# USB_OTG_FS.net
KiCad netlist of a schematic drawn in Altium Designer
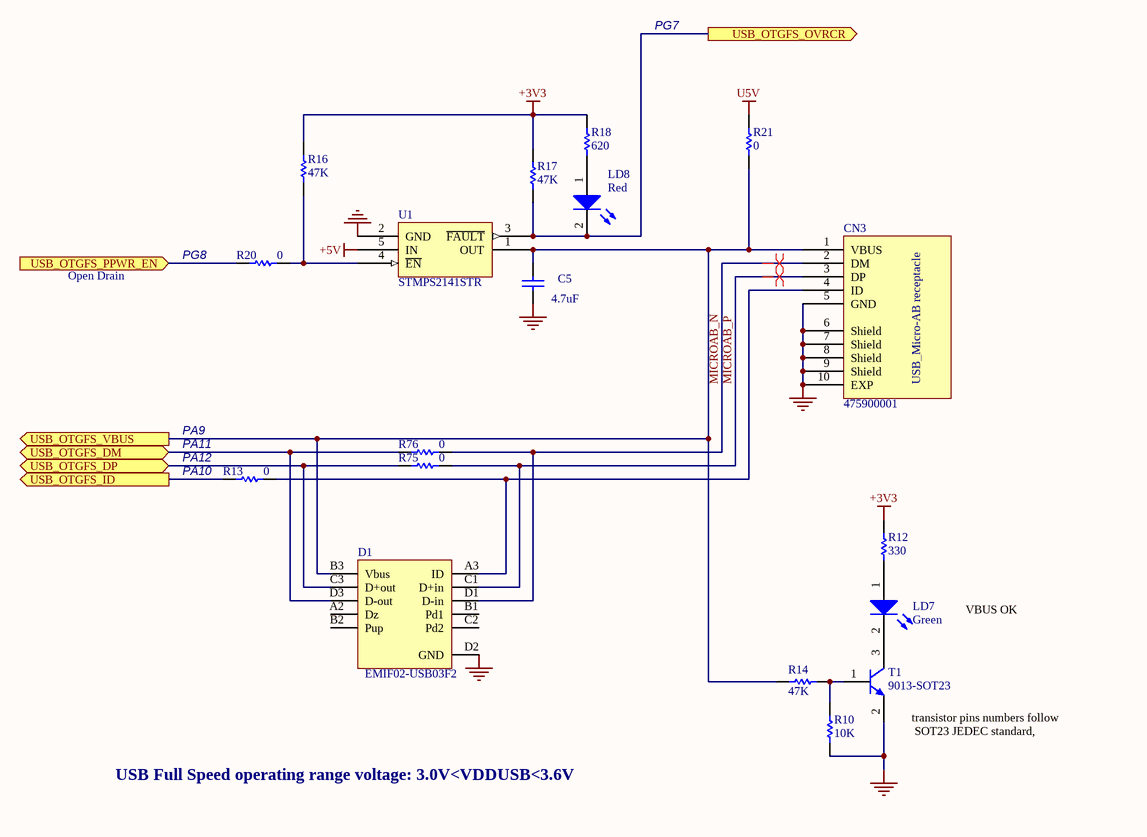
[diagram p0: USB_OTG_FS.SchDoc]

(export (version "E")
  (design (tool "Eeschema 10.0.6"))
  (components
    (comp (ref "C5")
      (value "4.7uF")
      (footprint "0603C")
      (description "Capacitor")
      (fields (field (name "PUBLISHER") "Altium Limited"))
      (libsource (lib "Miscellaneous Devices") (part "CAP"))
    )
    (comp (ref "CN3")
      (value "475900001")
      (footprint "MOLEX_47590001")
      (libsource (lib "mb1045") (part "475900001"))
    )
    (comp (ref "D1")
      (value "EMIF02-USB03F2")
      (footprint "BGA11_0R5_1R57X2R07")
      (libsource (lib "mb1045") (part "EMIF02-USB03F2"))
    )
    (comp (ref "LD7")
      (value "Green")
      (footprint "0603D")
      (description "Typical RED, GREEN, YELLOW, AMBER GaAs LED")
      (fields (field (name "PUBLISHER") "Altium Limited"))
      (libsource (lib "Miscellaneous Devices") (part "LED2"))
    )
    (comp (ref "LD8")
      (value "Red")
      (footprint "0603D")
      (description "Typical RED, GREEN, YELLOW, AMBER GaAs LED")
      (fields (field (name "PUBLISHER") "Altium Limited"))
      (libsource (lib "Miscellaneous Devices") (part "LED2"))
    )
    (comp (ref "R10")
      (value "10K")
      (footprint "0402R")
      (description "Resistor")
      (fields (field (name "PUBLISHER") "Altium Limited"))
      (libsource (lib "Miscellaneous Devices") (part "res1"))
    )
    (comp (ref "R12")
      (value "330")
      (footprint "0402R")
      (description "Resistor")
      (fields (field (name "PUBLISHER") "Altium Limited"))
      (libsource (lib "Miscellaneous Devices") (part "res1"))
    )
    (comp (ref "R13")
      (value "0")
      (footprint "SB_0603")
      (description "Resistor")
      (fields (field (name "PUBLISHER") "Altium Limited"))
      (libsource (lib "Miscellaneous Devices") (part "Res1"))
    )
    (comp (ref "R14")
      (value "47K")
      (footprint "0402R")
      (description "Resistor")
      (fields (field (name "PUBLISHER") "Altium Limited"))
      (libsource (lib "Miscellaneous Devices") (part "res1"))
    )
    (comp (ref "R16")
      (value "47K")
      (footprint "0402R")
      (description "Resistor")
      (fields (field (name "PUBLISHER") "Altium Limited"))
      (libsource (lib "Miscellaneous Devices") (part "res1"))
    )
    (comp (ref "R17")
      (value "47K")
      (footprint "0402R")
      (description "Resistor")
      (fields (field (name "PUBLISHER") "Altium Limited"))
      (libsource (lib "Miscellaneous Devices") (part "res1"))
    )
    (comp (ref "R18")
      (value "620")
      (footprint "0402R")
      (description "Resistor")
      (fields (field (name "PUBLISHER") "Altium Limited"))
      (libsource (lib "Miscellaneous Devices") (part "res1"))
    )
    (comp (ref "R20")
      (value "0")
      (footprint "SB_0603")
      (description "Resistor")
      (fields (field (name "PUBLISHER") "Altium Limited"))
      (libsource (lib "Miscellaneous Devices") (part "Res1"))
    )
    (comp (ref "R21")
      (value "0")
      (footprint "SB_0603")
      (description "Resistor")
      (fields (field (name "PUBLISHER") "Altium Limited"))
      (libsource (lib "Miscellaneous Devices") (part "Res1"))
    )
    (comp (ref "R75")
      (value "0")
      (footprint "SB_0603")
      (description "Resistor")
      (fields (field (name "PUBLISHER") "Altium Limited"))
      (libsource (lib "Miscellaneous Devices") (part "Res1"))
    )
    (comp (ref "R76")
      (value "0")
      (footprint "SB_0603")
      (description "Resistor")
      (fields (field (name "PUBLISHER") "Altium Limited"))
      (libsource (lib "Miscellaneous Devices") (part "Res1"))
    )
    (comp (ref "T1")
      (value "9013-SOT23")
      (footprint "SOT-23")
      (description "NPN Bipolar Transistor")
      (fields (field (name "PUBLISHER") "Altium Limited"))
      (libsource (lib "MB1167") (part "NPN"))
    )
    (comp (ref "U1")
      (value "STMPS2141STR")
      (footprint "SOT23-5")
      (description "Enhanced single channel power switches")
      (libsource (lib "MCD_TOOLS") (part "STMPS2141STR"))
    )
  )
  (nets
    (net (code "1") (name "+3V3") (class "Default")
      (node (ref "R12") (pin "1") (pinfunction "1_1") (pintype "passive"))
      (node (ref "R16") (pin "1") (pinfunction "1_1") (pintype "passive"))
      (node (ref "R17") (pin "1") (pinfunction "1_1") (pintype "passive"))
      (node (ref "R18") (pin "1") (pinfunction "1_1") (pintype "passive"))
    )
    (net (code "2") (name "+5V") (class "Default")
      (node (ref "U1") (pin "5") (pinfunction "IN_5") (pintype "passive"))
    )
    (net (code "3") (name "/MICROAB_N") (class "Default")
      (node (ref "CN3") (pin "2") (pinfunction "DM_2") (pintype "passive"))
      (node (ref "D1") (pin "D1") (pinfunction "D-in_D1") (pintype "passive"))
      (node (ref "R76") (pin "1") (pinfunction "1_1") (pintype "passive"))
    )
    (net (code "4") (name "/MICROAB_P") (class "Default")
      (node (ref "CN3") (pin "3") (pinfunction "DP_3") (pintype "passive"))
      (node (ref "D1") (pin "C1") (pinfunction "D+in_C1") (pintype "passive"))
      (node (ref "R75") (pin "1") (pinfunction "1_1") (pintype "passive"))
    )
    (net (code "5") (name "/USB_OTGFS_DM") (class "Default")
      (node (ref "D1") (pin "D3") (pinfunction "D-out_D3") (pintype "passive"))
      (node (ref "R76") (pin "2") (pinfunction "2_2") (pintype "passive"))
    )
    (net (code "6") (name "/USB_OTGFS_DP") (class "Default")
      (node (ref "D1") (pin "C3") (pinfunction "D+out_C3") (pintype "passive"))
      (node (ref "R75") (pin "2") (pinfunction "2_2") (pintype "passive"))
    )
    (net (code "7") (name "/USB_OTGFS_ID") (class "Default")
      (node (ref "R13") (pin "2") (pinfunction "2_2") (pintype "passive"))
    )
    (net (code "8") (name "/USB_OTGFS_OVRCR") (class "Default")
      (node (ref "LD8") (pin "2") (pinfunction "K_2") (pintype "passive"))
      (node (ref "R17") (pin "2") (pinfunction "2_2") (pintype "passive"))
      (node (ref "U1") (pin "3") (pinfunction "~{FAULT}_3") (pintype "output"))
    )
    (net (code "9") (name "/USB_OTGFS_PPWR_EN") (class "Default")
      (node (ref "R20") (pin "2") (pinfunction "2_2") (pintype "passive"))
    )
    (net (code "10") (name "/USB_OTGFS_VBUS") (class "Default")
      (node (ref "C5") (pin "1") (pinfunction "1_1") (pintype "passive"))
      (node (ref "CN3") (pin "1") (pinfunction "VBUS_1") (pintype "passive"))
      (node (ref "D1") (pin "B3") (pinfunction "Vbus_B3") (pintype "passive"))
      (node (ref "R14") (pin "1") (pinfunction "1_1") (pintype "passive"))
      (node (ref "R21") (pin "2") (pinfunction "2_2") (pintype "passive"))
      (node (ref "U1") (pin "1") (pinfunction "OUT_1") (pintype "passive"))
    )
    (net (code "11") (name "GND") (class "Default")
      (node (ref "C5") (pin "2") (pinfunction "2_2") (pintype "passive"))
      (node (ref "CN3") (pin "10") (pinfunction "EXP_10") (pintype "passive"))
      (node (ref "CN3") (pin "5") (pinfunction "GND_5") (pintype "passive"))
      (node (ref "CN3") (pin "6") (pinfunction "Shield_6") (pintype "passive"))
      (node (ref "CN3") (pin "7") (pinfunction "Shield_7") (pintype "passive"))
      (node (ref "CN3") (pin "8") (pinfunction "Shield_8") (pintype "passive"))
      (node (ref "CN3") (pin "9") (pinfunction "Shield_9") (pintype "passive"))
      (node (ref "D1") (pin "D2") (pinfunction "GND_D2") (pintype "passive"))
      (node (ref "R10") (pin "2") (pinfunction "2_2") (pintype "passive"))
      (node (ref "T1") (pin "2") (pinfunction "E_2") (pintype "passive"))
      (node (ref "U1") (pin "2") (pinfunction "GND_2") (pintype "passive"))
    )
    (net (code "12") (name "Net-(CN3-ID)") (class "Default")
      (node (ref "CN3") (pin "4") (pinfunction "ID_4") (pintype "passive"))
      (node (ref "D1") (pin "A3") (pinfunction "ID_A3") (pintype "passive"))
      (node (ref "R13") (pin "1") (pinfunction "1_1") (pintype "passive"))
    )
    (net (code "13") (name "Net-(LD7-A)") (class "Default")
      (node (ref "LD7") (pin "1") (pinfunction "A_1") (pintype "passive"))
      (node (ref "R12") (pin "2") (pinfunction "2_2") (pintype "passive"))
    )
    (net (code "14") (name "Net-(LD7-K)") (class "Default")
      (node (ref "LD7") (pin "2") (pinfunction "K_2") (pintype "passive"))
      (node (ref "T1") (pin "3") (pinfunction "C_3") (pintype "passive"))
    )
    (net (code "15") (name "Net-(LD8-A)") (class "Default")
      (node (ref "LD8") (pin "1") (pinfunction "A_1") (pintype "passive"))
      (node (ref "R18") (pin "2") (pinfunction "2_2") (pintype "passive"))
    )
    (net (code "16") (name "Net-(T1-B)") (class "Default")
      (node (ref "R10") (pin "1") (pinfunction "1_1") (pintype "passive"))
      (node (ref "R14") (pin "2") (pinfunction "2_2") (pintype "passive"))
      (node (ref "T1") (pin "1") (pinfunction "B_1") (pintype "passive"))
    )
    (net (code "17") (name "Net-(U1-~{EN})") (class "Default")
      (node (ref "R16") (pin "2") (pinfunction "2_2") (pintype "passive"))
      (node (ref "R20") (pin "1") (pinfunction "1_1") (pintype "passive"))
      (node (ref "U1") (pin "4") (pinfunction "~{EN}_4") (pintype "input"))
    )
    (net (code "18") (name "U5V") (class "Default")
      (node (ref "R21") (pin "1") (pinfunction "1_1") (pintype "passive"))
    )
    (net (code "19") (name "unconnected-(D1-Dz-PadA2)") (class "Default")
      (node (ref "D1") (pin "A2") (pinfunction "Dz_A2") (pintype "passive"))
    )
    (net (code "20") (name "unconnected-(D1-Pd1-PadB1)") (class "Default")
      (node (ref "D1") (pin "B1") (pinfunction "Pd1_B1") (pintype "passive"))
    )
    (net (code "21") (name "unconnected-(D1-Pd2-PadC2)") (class "Default")
      (node (ref "D1") (pin "C2") (pinfunction "Pd2_C2") (pintype "passive"))
    )
    (net (code "22") (name "unconnected-(D1-Pup-PadB2)") (class "Default")
      (node (ref "D1") (pin "B2") (pinfunction "Pup_B2") (pintype "passive"))
    )
  )
)
